# Sheet1.net
KiCad netlist of a schematic drawn in Altium Designer
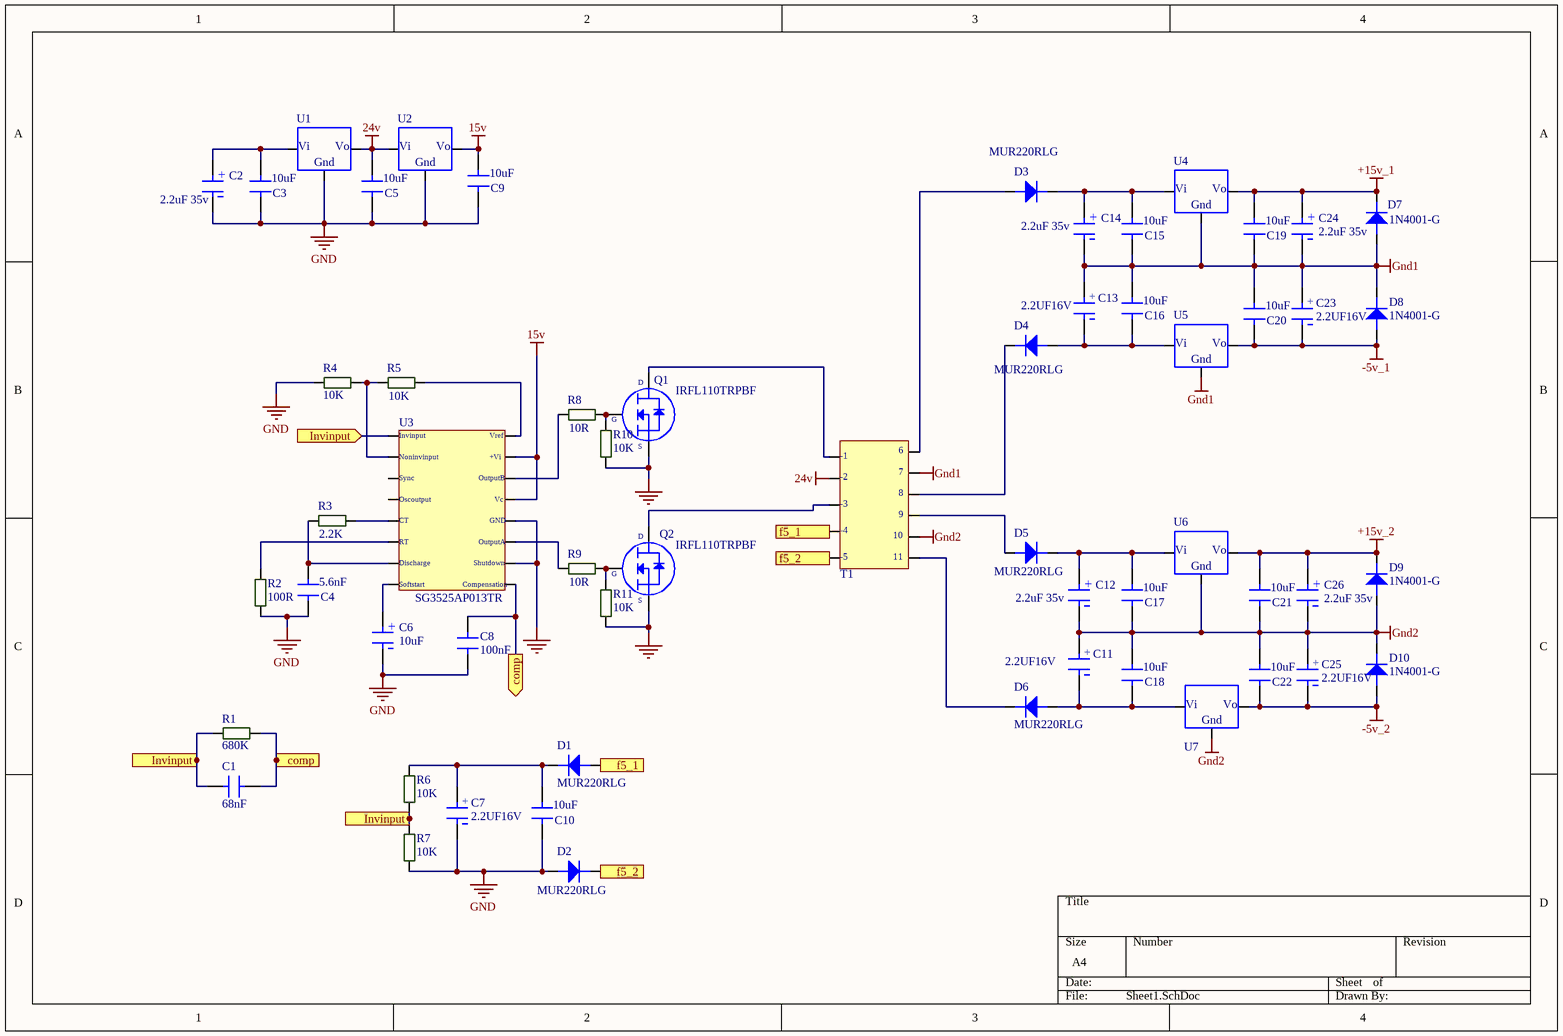
[diagram p0: Sheet1.SchDoc]

(export (version "E")
  (design (tool "Eeschema 10.0.6"))
  (components
    (comp (ref "C1")
      (value "68nF")
      (description "Cap Ceramic 10uF 50V X5R 10% SMD 1206 85C T/R")
      (fields
        (field (name "MANUFACTURER") "Samsung")
        (field (name "MANUFACTURER PART NUMBER") "CL31A106KBHNNNE")
      )
      (libsource (lib "Schlib1") (part "CL31A106KBHNNNE"))
    )
    (comp (ref "C2")
      (value "2.2uF 35v")
      (description "CAP TANT 2.2UF 35V 10% 1206")
      (fields
        (field (name "MANUFACTURER") "KEMET")
        (field (name "MANUFACTURER PART NUMBER") "T491A225K035AT")
      )
      (libsource (lib "Schlib1") (part "T491A225K035AT"))
    )
    (comp (ref "C3")
      (value "10uF")
      (description "Cap Ceramic 10uF 50V X5R 10% SMD 1206 85C T/R")
      (fields
        (field (name "MANUFACTURER") "Samsung")
        (field (name "MANUFACTURER PART NUMBER") "CL31A106KBHNNNE")
      )
      (libsource (lib "Schlib1") (part "CL31A106KBHNNNE"))
    )
    (comp (ref "C4")
      (value "5.6nF")
      (description "Cap Ceramic 10uF 50V X5R 10% SMD 1206 85C T/R")
      (fields
        (field (name "MANUFACTURER") "Samsung")
        (field (name "MANUFACTURER PART NUMBER") "CL31A106KBHNNNE")
      )
      (libsource (lib "Schlib1") (part "CL31A106KBHNNNE"))
    )
    (comp (ref "C5")
      (value "10uF")
      (description "Cap Ceramic 10uF 50V X5R 10% SMD 1206 85C T/R")
      (fields
        (field (name "MANUFACTURER") "Samsung")
        (field (name "MANUFACTURER PART NUMBER") "CL31A106KBHNNNE")
      )
      (libsource (lib "Schlib1") (part "CL31A106KBHNNNE"))
    )
    (comp (ref "C6")
      (value "10uF")
      (description "CAP TANT 2.2UF 35V 10% 1206")
      (fields
        (field (name "MANUFACTURER") "KEMET")
        (field (name "MANUFACTURER PART NUMBER") "T491A225K035AT")
      )
      (libsource (lib "Schlib1") (part "T491A225K035AT"))
    )
    (comp (ref "C7")
      (value "2.2UF16V")
      (description "CAP TANT 2.2UF 10% 16V 1206")
      (fields
        (field (name "MANUFACTURER") "KEMET")
        (field (name "MANUFACTURER PART NUMBER") "T491A225K016AT")
      )
      (libsource (lib "Schlib1") (part "T491A225K016AT"))
    )
    (comp (ref "C8")
      (value "100nF")
      (description "Cap Ceramic 10uF 50V X5R 10% SMD 1206 85C T/R")
      (fields
        (field (name "MANUFACTURER") "Samsung")
        (field (name "MANUFACTURER PART NUMBER") "CL31A106KBHNNNE")
      )
      (libsource (lib "Schlib1") (part "CL31A106KBHNNNE"))
    )
    (comp (ref "C9")
      (value "10uF")
      (description "Cap Ceramic 10uF 50V X5R 10% SMD 1206 85C T/R")
      (fields
        (field (name "MANUFACTURER") "Samsung")
        (field (name "MANUFACTURER PART NUMBER") "CL31A106KBHNNNE")
      )
      (libsource (lib "Schlib1") (part "CL31A106KBHNNNE"))
    )
    (comp (ref "C10")
      (value "10uF")
      (description "Cap Ceramic 10uF 50V X5R 10% SMD 1206 85C T/R")
      (fields
        (field (name "MANUFACTURER") "Samsung")
        (field (name "MANUFACTURER PART NUMBER") "CL31A106KBHNNNE")
      )
      (libsource (lib "Schlib1") (part "CL31A106KBHNNNE"))
    )
    (comp (ref "C11")
      (value "2.2UF16V")
      (description "CAP TANT 2.2UF 10% 16V 1206")
      (fields
        (field (name "MANUFACTURER") "KEMET")
        (field (name "MANUFACTURER PART NUMBER") "T491A225K016AT")
      )
      (libsource (lib "Schlib1") (part "T491A225K016AT"))
    )
    (comp (ref "C12")
      (value "2.2uF 35v")
      (description "CAP TANT 2.2UF 35V 10% 1206")
      (fields
        (field (name "MANUFACTURER") "KEMET")
        (field (name "MANUFACTURER PART NUMBER") "T491A225K035AT")
      )
      (libsource (lib "Schlib1") (part "T491A225K035AT"))
    )
    (comp (ref "C13")
      (value "2.2UF16V")
      (description "CAP TANT 2.2UF 10% 16V 1206")
      (fields
        (field (name "MANUFACTURER") "KEMET")
        (field (name "MANUFACTURER PART NUMBER") "T491A225K016AT")
      )
      (libsource (lib "Schlib1") (part "T491A225K016AT"))
    )
    (comp (ref "C14")
      (value "2.2uF 35v")
      (description "CAP TANT 2.2UF 35V 10% 1206")
      (fields
        (field (name "MANUFACTURER") "KEMET")
        (field (name "MANUFACTURER PART NUMBER") "T491A225K035AT")
      )
      (libsource (lib "Schlib1") (part "T491A225K035AT"))
    )
    (comp (ref "C15")
      (value "10uF")
      (description "Cap Ceramic 10uF 50V X5R 10% SMD 1206 85C T/R")
      (fields
        (field (name "MANUFACTURER") "Samsung")
        (field (name "MANUFACTURER PART NUMBER") "CL31A106KBHNNNE")
      )
      (libsource (lib "Schlib1") (part "CL31A106KBHNNNE"))
    )
    (comp (ref "C16")
      (value "10uF")
      (description "Cap Ceramic 10uF 50V X5R 10% SMD 1206 85C T/R")
      (fields
        (field (name "MANUFACTURER") "Samsung")
        (field (name "MANUFACTURER PART NUMBER") "CL31A106KBHNNNE")
      )
      (libsource (lib "Schlib1") (part "CL31A106KBHNNNE"))
    )
    (comp (ref "C17")
      (value "10uF")
      (description "Cap Ceramic 10uF 50V X5R 10% SMD 1206 85C T/R")
      (fields
        (field (name "MANUFACTURER") "Samsung")
        (field (name "MANUFACTURER PART NUMBER") "CL31A106KBHNNNE")
      )
      (libsource (lib "Schlib1") (part "CL31A106KBHNNNE"))
    )
    (comp (ref "C18")
      (value "10uF")
      (description "Cap Ceramic 10uF 50V X5R 10% SMD 1206 85C T/R")
      (fields
        (field (name "MANUFACTURER") "Samsung")
        (field (name "MANUFACTURER PART NUMBER") "CL31A106KBHNNNE")
      )
      (libsource (lib "Schlib1") (part "CL31A106KBHNNNE"))
    )
    (comp (ref "C19")
      (value "10uF")
      (description "Cap Ceramic 10uF 50V X5R 10% SMD 1206 85C T/R")
      (fields
        (field (name "MANUFACTURER") "Samsung")
        (field (name "MANUFACTURER PART NUMBER") "CL31A106KBHNNNE")
      )
      (libsource (lib "Schlib1") (part "CL31A106KBHNNNE"))
    )
    (comp (ref "C20")
      (value "10uF")
      (description "Cap Ceramic 10uF 50V X5R 10% SMD 1206 85C T/R")
      (fields
        (field (name "MANUFACTURER") "Samsung")
        (field (name "MANUFACTURER PART NUMBER") "CL31A106KBHNNNE")
      )
      (libsource (lib "Schlib1") (part "CL31A106KBHNNNE"))
    )
    (comp (ref "C21")
      (value "10uF")
      (description "Cap Ceramic 10uF 50V X5R 10% SMD 1206 85C T/R")
      (fields
        (field (name "MANUFACTURER") "Samsung")
        (field (name "MANUFACTURER PART NUMBER") "CL31A106KBHNNNE")
      )
      (libsource (lib "Schlib1") (part "CL31A106KBHNNNE"))
    )
    (comp (ref "C22")
      (value "10uF")
      (description "Cap Ceramic 10uF 50V X5R 10% SMD 1206 85C T/R")
      (fields
        (field (name "MANUFACTURER") "Samsung")
        (field (name "MANUFACTURER PART NUMBER") "CL31A106KBHNNNE")
      )
      (libsource (lib "Schlib1") (part "CL31A106KBHNNNE"))
    )
    (comp (ref "C23")
      (value "2.2UF16V")
      (description "CAP TANT 2.2UF 10% 16V 1206")
      (fields
        (field (name "MANUFACTURER") "KEMET")
        (field (name "MANUFACTURER PART NUMBER") "T491A225K016AT")
      )
      (libsource (lib "Schlib1") (part "T491A225K016AT"))
    )
    (comp (ref "C24")
      (value "2.2uF 35v")
      (description "CAP TANT 2.2UF 35V 10% 1206")
      (fields
        (field (name "MANUFACTURER") "KEMET")
        (field (name "MANUFACTURER PART NUMBER") "T491A225K035AT")
      )
      (libsource (lib "Schlib1") (part "T491A225K035AT"))
    )
    (comp (ref "C25")
      (value "2.2UF16V")
      (description "CAP TANT 2.2UF 10% 16V 1206")
      (fields
        (field (name "MANUFACTURER") "KEMET")
        (field (name "MANUFACTURER PART NUMBER") "T491A225K016AT")
      )
      (libsource (lib "Schlib1") (part "T491A225K016AT"))
    )
    (comp (ref "C26")
      (value "2.2uF 35v")
      (description "CAP TANT 2.2UF 35V 10% 1206")
      (fields
        (field (name "MANUFACTURER") "KEMET")
        (field (name "MANUFACTURER PART NUMBER") "T491A225K035AT")
      )
      (libsource (lib "Schlib1") (part "T491A225K035AT"))
    )
    (comp (ref "D1")
      (value "MUR220RLG")
      (description "DIODE GEN PURP 200V 2A AXIAL")
      (fields (field (name "MANUFACTURER") "ON Semiconductor"))
      (libsource (lib "Schlib1") (part "MUR220RLG"))
    )
    (comp (ref "D2")
      (value "MUR220RLG")
      (description "DIODE GEN PURP 200V 2A AXIAL")
      (fields (field (name "MANUFACTURER") "ON Semiconductor"))
      (libsource (lib "Schlib1") (part "MUR220RLG"))
    )
    (comp (ref "D3")
      (value "MUR220RLG")
      (description "DIODE GEN PURP 200V 2A AXIAL")
      (fields (field (name "MANUFACTURER") "ON Semiconductor"))
      (libsource (lib "Schlib1") (part "MUR220RLG"))
    )
    (comp (ref "D4")
      (value "MUR220RLG")
      (description "DIODE GEN PURP 200V 2A AXIAL")
      (fields (field (name "MANUFACTURER") "ON Semiconductor"))
      (libsource (lib "Schlib1") (part "MUR220RLG"))
    )
    (comp (ref "D5")
      (value "MUR220RLG")
      (description "DIODE GEN PURP 200V 2A AXIAL")
      (fields (field (name "MANUFACTURER") "ON Semiconductor"))
      (libsource (lib "Schlib1") (part "MUR220RLG"))
    )
    (comp (ref "D6")
      (value "MUR220RLG")
      (description "DIODE GEN PURP 200V 2A AXIAL")
      (fields (field (name "MANUFACTURER") "ON Semiconductor"))
      (libsource (lib "Schlib1") (part "MUR220RLG"))
    )
    (comp (ref "D7")
      (value "1N4001-G")
      (description "DIODE GEN PURP 50V 1A DO41")
      (fields (field (name "MANUFACTURER") "Comchip"))
      (libsource (lib "Schlib1") (part "1N4001-G"))
    )
    (comp (ref "D8")
      (value "1N4001-G")
      (description "DIODE GEN PURP 50V 1A DO41")
      (fields (field (name "MANUFACTURER") "Comchip"))
      (libsource (lib "Schlib1") (part "1N4001-G"))
    )
    (comp (ref "D9")
      (value "1N4001-G")
      (description "DIODE GEN PURP 50V 1A DO41")
      (fields (field (name "MANUFACTURER") "Comchip"))
      (libsource (lib "Schlib1") (part "1N4001-G"))
    )
    (comp (ref "D10")
      (value "1N4001-G")
      (description "DIODE GEN PURP 50V 1A DO41")
      (fields (field (name "MANUFACTURER") "Comchip"))
      (libsource (lib "Schlib1") (part "1N4001-G"))
    )
    (comp (ref "Q1")
      (value "IRFL110TRPBF")
      (description "Trans MOSFET N-CH 100V 1.5A 4-Pin(3+Tab) SOT-223 T/R")
      (fields (field (name "MANUFACTURER") "Vishay") (field (name "VOLTAGE") "100V"))
      (libsource (lib "Schlib1") (part "IRFL110TRPBF"))
    )
    (comp (ref "Q2")
      (value "IRFL110TRPBF")
      (description "Trans MOSFET N-CH 100V 1.5A 4-Pin(3+Tab) SOT-223 T/R")
      (fields (field (name "MANUFACTURER") "Vishay") (field (name "VOLTAGE") "100V"))
      (libsource (lib "Schlib1") (part "IRFL110TRPBF"))
    )
    (comp (ref "R1")
      (value "680K")
      (description "RES 0 OHM JUMPER 1/4W 1206")
      (fields
        (field (name "MANUFACTURER") "Stackpole Electronics")
        (field (name "MANUFACTURER PART NUMBER") "RMCF1206ZT0R00")
      )
      (libsource (lib "Schlib1") (part "RMCF1206ZT0R00"))
    )
    (comp (ref "R2")
      (value "100R")
      (description "RES 0 OHM JUMPER 1/4W 1206")
      (fields
        (field (name "MANUFACTURER") "Stackpole Electronics")
        (field (name "MANUFACTURER PART NUMBER") "RMCF1206ZT0R00")
      )
      (libsource (lib "Schlib1") (part "RMCF1206ZT0R00"))
    )
    (comp (ref "R3")
      (value "2.2K")
      (description "RES 0 OHM JUMPER 1/4W 1206")
      (fields
        (field (name "MANUFACTURER") "Stackpole Electronics")
        (field (name "MANUFACTURER PART NUMBER") "RMCF1206ZT0R00")
      )
      (libsource (lib "Schlib1") (part "RMCF1206ZT0R00"))
    )
    (comp (ref "R4")
      (value "10K")
      (description "RES 0 OHM JUMPER 1/4W 1206")
      (fields
        (field (name "MANUFACTURER") "Stackpole Electronics")
        (field (name "MANUFACTURER PART NUMBER") "RMCF1206ZT0R00")
      )
      (libsource (lib "Schlib1") (part "RMCF1206ZT0R00"))
    )
    (comp (ref "R5")
      (value "10K")
      (description "RES 0 OHM JUMPER 1/4W 1206")
      (fields
        (field (name "MANUFACTURER") "Stackpole Electronics")
        (field (name "MANUFACTURER PART NUMBER") "RMCF1206ZT0R00")
      )
      (libsource (lib "Schlib1") (part "RMCF1206ZT0R00"))
    )
    (comp (ref "R6")
      (value "10K")
      (description "RES 0 OHM JUMPER 1/4W 1206")
      (fields
        (field (name "MANUFACTURER") "Stackpole Electronics")
        (field (name "MANUFACTURER PART NUMBER") "RMCF1206ZT0R00")
      )
      (libsource (lib "Schlib1") (part "RMCF1206ZT0R00"))
    )
    (comp (ref "R7")
      (value "10K")
      (description "RES 0 OHM JUMPER 1/4W 1206")
      (fields
        (field (name "MANUFACTURER") "Stackpole Electronics")
        (field (name "MANUFACTURER PART NUMBER") "RMCF1206ZT0R00")
      )
      (libsource (lib "Schlib1") (part "RMCF1206ZT0R00"))
    )
    (comp (ref "R8")
      (value "10R")
      (description "RES 0 OHM JUMPER 1/4W 1206")
      (fields
        (field (name "MANUFACTURER") "Stackpole Electronics")
        (field (name "MANUFACTURER PART NUMBER") "RMCF1206ZT0R00")
      )
      (libsource (lib "Schlib1") (part "RMCF1206ZT0R00"))
    )
    (comp (ref "R9")
      (value "10R")
      (description "RES 0 OHM JUMPER 1/4W 1206")
      (fields
        (field (name "MANUFACTURER") "Stackpole Electronics")
        (field (name "MANUFACTURER PART NUMBER") "RMCF1206ZT0R00")
      )
      (libsource (lib "Schlib1") (part "RMCF1206ZT0R00"))
    )
    (comp (ref "R10")
      (value "10K")
      (description "RES 0 OHM JUMPER 1/4W 1206")
      (fields
        (field (name "MANUFACTURER") "Stackpole Electronics")
        (field (name "MANUFACTURER PART NUMBER") "RMCF1206ZT0R00")
      )
      (libsource (lib "Schlib1") (part "RMCF1206ZT0R00"))
    )
    (comp (ref "R11")
      (value "10K")
      (description "RES 0 OHM JUMPER 1/4W 1206")
      (fields
        (field (name "MANUFACTURER") "Stackpole Electronics")
        (field (name "MANUFACTURER PART NUMBER") "RMCF1206ZT0R00")
      )
      (libsource (lib "Schlib1") (part "RMCF1206ZT0R00"))
    )
    (comp (ref "T1") (value "EE2006Transformer") (libsource (lib "Schlib1") (part "EE2006Transformer")))
    (comp (ref "U1")
      (value "L78M24CDT-TR")
      (description "IC REG LINEAR 24V 500MA DPAK")
      (fields (field (name "MANUFACTURER") "STMicroelectronics"))
      (libsource (lib "Schlib1") (part "L78M24CDT-TR"))
    )
    (comp (ref "U2")
      (value "L78M15CDT")
      (description "Linear Voltage Regulators 15V 0.5A Positive")
      (fields (field (name "MANUFACTURER") "STMicroelectronics"))
      (libsource (lib "Schlib1") (part "L78M15CDT"))
    )
    (comp (ref "U3")
      (value "SG3525AP013TR")
      (description "IC REG CTRLR BCK/PSH-PULL 16SOIC")
      (fields (field (name "MANUFACTURER") "STMicroelectronics"))
      (libsource (lib "Schlib1") (part "SG3525AP013TR"))
    )
    (comp (ref "U4")
      (value "L78M15CDT")
      (description "Linear Voltage Regulators 15V 0.5A Positive")
      (fields (field (name "MANUFACTURER") "STMicroelectronics"))
      (libsource (lib "Schlib1") (part "L78M15CDT"))
    )
    (comp (ref "U5")
      (value "MC79M05CDTRKG")
      (description "ON SEMICONDUCTOR - MC79M05CDTRKG - NEGATIVE VOLTAGE REGULATOR, -5V, DPAK-3")
      (fields (field (name "MANUFACTURER") "ON Semiconductor"))
      (libsource (lib "Schlib1") (part "MC79M05CDTRKG"))
    )
    (comp (ref "U6")
      (value "L78M15CDT")
      (description "Linear Voltage Regulators 15V 0.5A Positive")
      (fields (field (name "MANUFACTURER") "STMicroelectronics"))
      (libsource (lib "Schlib1") (part "L78M15CDT"))
    )
    (comp (ref "U7")
      (value "MC79M05CDTRKG")
      (description "ON SEMICONDUCTOR - MC79M05CDTRKG - NEGATIVE VOLTAGE REGULATOR, -5V, DPAK-3")
      (fields (field (name "MANUFACTURER") "ON Semiconductor"))
      (libsource (lib "Schlib1") (part "MC79M05CDTRKG"))
    )
  )
  (nets
    (net (code "1") (name "+15v_1") (class "Default")
      (node (ref "C19") (pin "3") (pinfunction "3_3") (pintype "passive"))
      (node (ref "C24") (pin "1") (pinfunction "1_1") (pintype "passive"))
      (node (ref "D7") (pin "1") (pinfunction "1_1") (pintype "passive"))
      (node (ref "U4") (pin "3") (pinfunction "3_3") (pintype "passive"))
    )
    (net (code "2") (name "+15v_2") (class "Default")
      (node (ref "C21") (pin "3") (pinfunction "3_3") (pintype "passive"))
      (node (ref "C26") (pin "1") (pinfunction "1_1") (pintype "passive"))
      (node (ref "D9") (pin "1") (pinfunction "1_1") (pintype "passive"))
      (node (ref "U6") (pin "3") (pinfunction "3_3") (pintype "passive"))
    )
    (net (code "3") (name "-5v_1") (class "Default")
      (node (ref "C20") (pin "4") (pinfunction "4_4") (pintype "passive"))
      (node (ref "C23") (pin "2") (pinfunction "2_2") (pintype "passive"))
      (node (ref "D8") (pin "2") (pinfunction "2_2") (pintype "passive"))
      (node (ref "U5") (pin "2") (pinfunction "2_2") (pintype "passive"))
    )
    (net (code "4") (name "-5v_2") (class "Default")
      (node (ref "C22") (pin "4") (pinfunction "4_4") (pintype "passive"))
      (node (ref "C25") (pin "2") (pinfunction "2_2") (pintype "passive"))
      (node (ref "D10") (pin "2") (pinfunction "2_2") (pintype "passive"))
      (node (ref "U7") (pin "2") (pinfunction "2_2") (pintype "passive"))
    )
    (net (code "5") (name "/Invinput") (class "Default")
      (node (ref "C1") (pin "3") (pinfunction "3_3") (pintype "passive"))
      (node (ref "R1") (pin "2") (pinfunction "2_2") (pintype "passive"))
      (node (ref "R6") (pin "2") (pinfunction "2_2") (pintype "passive"))
      (node (ref "R7") (pin "1") (pinfunction "1_1") (pintype "passive"))
      (node (ref "U3") (pin "1") (pinfunction "1_1") (pintype "passive"))
    )
    (net (code "6") (name "/comp") (class "Default")
      (node (ref "C1") (pin "4") (pinfunction "4_4") (pintype "passive"))
      (node (ref "C8") (pin "4") (pinfunction "4_4") (pintype "passive"))
      (node (ref "R1") (pin "1") (pinfunction "1_1") (pintype "passive"))
      (node (ref "U3") (pin "9") (pinfunction "9_9") (pintype "passive"))
    )
    (net (code "7") (name "/f5_1") (class "Default")
      (node (ref "D1") (pin "2") (pinfunction "2_2") (pintype "passive"))
      (node (ref "T1") (pin "4") (pinfunction "4_4") (pintype "passive"))
    )
    (net (code "8") (name "/f5_2") (class "Default")
      (node (ref "D2") (pin "1") (pinfunction "1_1") (pintype "passive"))
      (node (ref "T1") (pin "5") (pinfunction "5_5") (pintype "passive"))
    )
    (net (code "9") (name "15v") (class "Default")
      (node (ref "C9") (pin "3") (pinfunction "3_3") (pintype "passive"))
      (node (ref "U2") (pin "3") (pinfunction "3_3") (pintype "passive"))
      (node (ref "U3") (pin "13") (pinfunction "13_13") (pintype "passive"))
      (node (ref "U3") (pin "15") (pinfunction "15_15") (pintype "passive"))
    )
    (net (code "10") (name "24v") (class "Default")
      (node (ref "C5") (pin "3") (pinfunction "3_3") (pintype "passive"))
      (node (ref "T1") (pin "2") (pinfunction "2_2") (pintype "passive"))
      (node (ref "U1") (pin "3") (pinfunction "3_3") (pintype "passive"))
      (node (ref "U2") (pin "1") (pinfunction "1_1") (pintype "passive"))
    )
    (net (code "11") (name "GND") (class "Default")
      (node (ref "C10") (pin "4") (pinfunction "4_4") (pintype "passive"))
      (node (ref "C2") (pin "2") (pinfunction "2_2") (pintype "passive"))
      (node (ref "C3") (pin "4") (pinfunction "4_4") (pintype "passive"))
      (node (ref "C4") (pin "4") (pinfunction "4_4") (pintype "passive"))
      (node (ref "C5") (pin "4") (pinfunction "4_4") (pintype "passive"))
      (node (ref "C6") (pin "2") (pinfunction "2_2") (pintype "passive"))
      (node (ref "C7") (pin "2") (pinfunction "2_2") (pintype "passive"))
      (node (ref "C8") (pin "3") (pinfunction "3_3") (pintype "passive"))
      (node (ref "C9") (pin "4") (pinfunction "4_4") (pintype "passive"))
      (node (ref "D2") (pin "2") (pinfunction "2_2") (pintype "passive"))
      (node (ref "Q1") (pin "2") (pinfunction "2_2") (pintype "passive"))
      (node (ref "Q2") (pin "2") (pinfunction "2_2") (pintype "passive"))
      (node (ref "R10") (pin "1") (pinfunction "1_1") (pintype "passive"))
      (node (ref "R11") (pin "2") (pinfunction "2_2") (pintype "passive"))
      (node (ref "R2") (pin "2") (pinfunction "2_2") (pintype "passive"))
      (node (ref "R4") (pin "2") (pinfunction "2_2") (pintype "passive"))
      (node (ref "R7") (pin "2") (pinfunction "2_2") (pintype "passive"))
      (node (ref "U1") (pin "2") (pinfunction "2_2") (pintype "passive"))
      (node (ref "U2") (pin "2") (pinfunction "2_2") (pintype "passive"))
      (node (ref "U3") (pin "10") (pinfunction "10_10") (pintype "passive"))
      (node (ref "U3") (pin "12") (pinfunction "12_12") (pintype "passive"))
    )
    (net (code "12") (name "Gnd1") (class "Default")
      (node (ref "C13") (pin "1") (pinfunction "1_1") (pintype "passive"))
      (node (ref "C14") (pin "2") (pinfunction "2_2") (pintype "passive"))
      (node (ref "C15") (pin "4") (pinfunction "4_4") (pintype "passive"))
      (node (ref "C16") (pin "3") (pinfunction "3_3") (pintype "passive"))
      (node (ref "C19") (pin "4") (pinfunction "4_4") (pintype "passive"))
      (node (ref "C20") (pin "3") (pinfunction "3_3") (pintype "passive"))
      (node (ref "C23") (pin "1") (pinfunction "1_1") (pintype "passive"))
      (node (ref "C24") (pin "2") (pinfunction "2_2") (pintype "passive"))
      (node (ref "D7") (pin "2") (pinfunction "2_2") (pintype "passive"))
      (node (ref "D8") (pin "1") (pinfunction "1_1") (pintype "passive"))
      (node (ref "T1") (pin "10") (pinfunction "10_10") (pintype "passive"))
      (node (ref "U4") (pin "2") (pinfunction "2_2") (pintype "passive"))
      (node (ref "U5") (pin "3") (pinfunction "3_3") (pintype "passive"))
    )
    (net (code "13") (name "Gnd2") (class "Default")
      (node (ref "C11") (pin "1") (pinfunction "1_1") (pintype "passive"))
      (node (ref "C12") (pin "2") (pinfunction "2_2") (pintype "passive"))
      (node (ref "C17") (pin "4") (pinfunction "4_4") (pintype "passive"))
      (node (ref "C18") (pin "3") (pinfunction "3_3") (pintype "passive"))
      (node (ref "C21") (pin "4") (pinfunction "4_4") (pintype "passive"))
      (node (ref "C22") (pin "3") (pinfunction "3_3") (pintype "passive"))
      (node (ref "C25") (pin "1") (pinfunction "1_1") (pintype "passive"))
      (node (ref "C26") (pin "2") (pinfunction "2_2") (pintype "passive"))
      (node (ref "D10") (pin "1") (pinfunction "1_1") (pintype "passive"))
      (node (ref "D9") (pin "2") (pinfunction "2_2") (pintype "passive"))
      (node (ref "T1") (pin "7") (pinfunction "7_7") (pintype "passive"))
      (node (ref "U6") (pin "2") (pinfunction "2_2") (pintype "passive"))
      (node (ref "U7") (pin "3") (pinfunction "3_3") (pintype "passive"))
    )
    (net (code "14") (name "Net-(C2-Pad1)") (class "Default")
      (node (ref "C2") (pin "1") (pinfunction "1_1") (pintype "passive"))
      (node (ref "C3") (pin "3") (pinfunction "3_3") (pintype "passive"))
      (node (ref "U1") (pin "1") (pinfunction "1_1") (pintype "passive"))
    )
    (net (code "15") (name "Net-(C4-Pad3)") (class "Default")
      (node (ref "C4") (pin "3") (pinfunction "3_3") (pintype "passive"))
      (node (ref "R3") (pin "2") (pinfunction "2_2") (pintype "passive"))
      (node (ref "U3") (pin "7") (pinfunction "7_7") (pintype "passive"))
    )
    (net (code "16") (name "Net-(C6-Pad1)") (class "Default")
      (node (ref "C6") (pin "1") (pinfunction "1_1") (pintype "passive"))
      (node (ref "U3") (pin "8") (pinfunction "8_8") (pintype "passive"))
    )
    (net (code "17") (name "Net-(C10-Pad3)") (class "Default")
      (node (ref "C10") (pin "3") (pinfunction "3_3") (pintype "passive"))
      (node (ref "C7") (pin "1") (pinfunction "1_1") (pintype "passive"))
      (node (ref "D1") (pin "1") (pinfunction "1_1") (pintype "passive"))
      (node (ref "R6") (pin "1") (pinfunction "1_1") (pintype "passive"))
    )
    (net (code "18") (name "Net-(C11-Pad2)") (class "Default")
      (node (ref "C11") (pin "2") (pinfunction "2_2") (pintype "passive"))
      (node (ref "C18") (pin "4") (pinfunction "4_4") (pintype "passive"))
      (node (ref "D6") (pin "2") (pinfunction "2_2") (pintype "passive"))
      (node (ref "U7") (pin "1") (pinfunction "1_1") (pintype "passive"))
    )
    (net (code "19") (name "Net-(C12-Pad1)") (class "Default")
      (node (ref "C12") (pin "1") (pinfunction "1_1") (pintype "passive"))
      (node (ref "C17") (pin "3") (pinfunction "3_3") (pintype "passive"))
      (node (ref "D5") (pin "1") (pinfunction "1_1") (pintype "passive"))
      (node (ref "U6") (pin "1") (pinfunction "1_1") (pintype "passive"))
    )
    (net (code "20") (name "Net-(C13-Pad2)") (class "Default")
      (node (ref "C13") (pin "2") (pinfunction "2_2") (pintype "passive"))
      (node (ref "C16") (pin "4") (pinfunction "4_4") (pintype "passive"))
      (node (ref "D4") (pin "2") (pinfunction "2_2") (pintype "passive"))
      (node (ref "U5") (pin "1") (pinfunction "1_1") (pintype "passive"))
    )
    (net (code "21") (name "Net-(C14-Pad1)") (class "Default")
      (node (ref "C14") (pin "1") (pinfunction "1_1") (pintype "passive"))
      (node (ref "C15") (pin "3") (pinfunction "3_3") (pintype "passive"))
      (node (ref "D3") (pin "1") (pinfunction "1_1") (pintype "passive"))
      (node (ref "U4") (pin "1") (pinfunction "1_1") (pintype "passive"))
    )
    (net (code "22") (name "Net-(D3-Pad2)") (class "Default")
      (node (ref "D3") (pin "2") (pinfunction "2_2") (pintype "passive"))
      (node (ref "T1") (pin "11") (pinfunction "11_11") (pintype "passive"))
    )
    (net (code "23") (name "Net-(D4-Pad1)") (class "Default")
      (node (ref "D4") (pin "1") (pinfunction "1_1") (pintype "passive"))
      (node (ref "T1") (pin "9") (pinfunction "9_9") (pintype "passive"))
    )
    (net (code "24") (name "Net-(D5-Pad2)") (class "Default")
      (node (ref "D5") (pin "2") (pinfunction "2_2") (pintype "passive"))
      (node (ref "T1") (pin "8") (pinfunction "8_8") (pintype "passive"))
    )
    (net (code "25") (name "Net-(D6-Pad1)") (class "Default")
      (node (ref "D6") (pin "1") (pinfunction "1_1") (pintype "passive"))
      (node (ref "T1") (pin "6") (pinfunction "6_6") (pintype "passive"))
    )
    (net (code "26") (name "Net-(Q1-Pad0)") (class "Default")
      (node (ref "Q1") (pin "0") (pinfunction "0_0") (pintype "passive"))
      (node (ref "R10") (pin "2") (pinfunction "2_2") (pintype "passive"))
      (node (ref "R8") (pin "1") (pinfunction "1_1") (pintype "passive"))
    )
    (net (code "27") (name "Net-(Q1-Pad1)") (class "Default")
      (node (ref "Q1") (pin "1") (pinfunction "1_1") (pintype "passive"))
      (node (ref "T1") (pin "1") (pinfunction "1_1") (pintype "passive"))
    )
    (net (code "28") (name "Net-(Q2-Pad0)") (class "Default")
      (node (ref "Q2") (pin "0") (pinfunction "0_0") (pintype "passive"))
      (node (ref "R11") (pin "1") (pinfunction "1_1") (pintype "passive"))
      (node (ref "R9") (pin "1") (pinfunction "1_1") (pintype "passive"))
    )
    (net (code "29") (name "Net-(Q2-Pad1)") (class "Default")
      (node (ref "Q2") (pin "1") (pinfunction "1_1") (pintype "passive"))
      (node (ref "T1") (pin "3") (pinfunction "3_3") (pintype "passive"))
    )
    (net (code "30") (name "Net-(R2-Pad1)") (class "Default")
      (node (ref "R2") (pin "1") (pinfunction "1_1") (pintype "passive"))
      (node (ref "U3") (pin "6") (pinfunction "6_6") (pintype "passive"))
    )
    (net (code "31") (name "Net-(R3-Pad1)") (class "Default")
      (node (ref "R3") (pin "1") (pinfunction "1_1") (pintype "passive"))
      (node (ref "U3") (pin "5") (pinfunction "5_5") (pintype "passive"))
    )
    (net (code "32") (name "Net-(R4-Pad1)") (class "Default")
      (node (ref "R4") (pin "1") (pinfunction "1_1") (pintype "passive"))
      (node (ref "R5") (pin "2") (pinfunction "2_2") (pintype "passive"))
      (node (ref "U3") (pin "2") (pinfunction "2_2") (pintype "passive"))
    )
    (net (code "33") (name "Net-(R5-Pad1)") (class "Default")
      (node (ref "R5") (pin "1") (pinfunction "1_1") (pintype "passive"))
      (node (ref "U3") (pin "16") (pinfunction "16_16") (pintype "passive"))
    )
    (net (code "34") (name "Net-(R8-Pad2)") (class "Default")
      (node (ref "R8") (pin "2") (pinfunction "2_2") (pintype "passive"))
      (node (ref "U3") (pin "14") (pinfunction "14_14") (pintype "passive"))
    )
    (net (code "35") (name "Net-(R9-Pad2)") (class "Default")
      (node (ref "R9") (pin "2") (pinfunction "2_2") (pintype "passive"))
      (node (ref "U3") (pin "11") (pinfunction "11_11") (pintype "passive"))
    )
    (net (code "36") (name "unconnected-(U3-Pad3)") (class "Default")
      (node (ref "U3") (pin "3") (pinfunction "3_3") (pintype "passive"))
    )
    (net (code "37") (name "unconnected-(U3-Pad4)") (class "Default")
      (node (ref "U3") (pin "4") (pinfunction "4_4") (pintype "passive"))
    )
  )
)
